# 5_5Vto5VBuck.net
KiCad netlist of a schematic drawn in Altium Designer
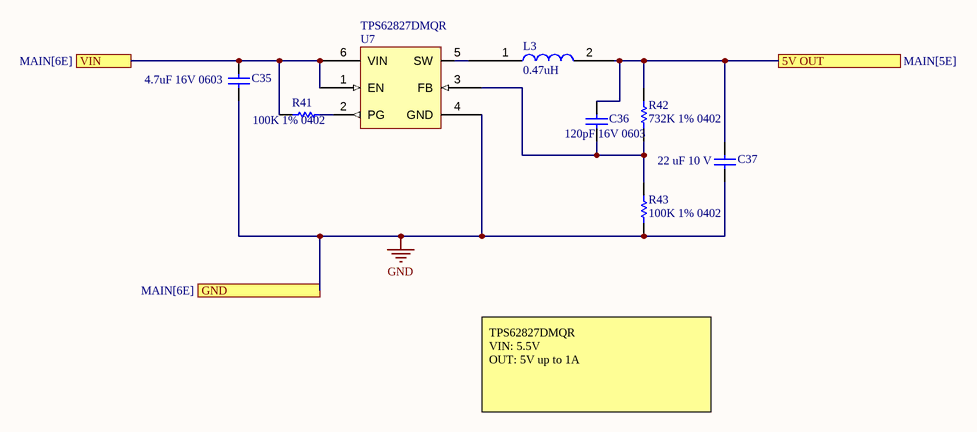
[diagram p0: 5.5Vto5VBuck.SchDoc]

(export (version "E")
  (design (tool "Eeschema 10.0.6"))
  (components
    (comp (ref "C35")
      (value "4.7uF 16V 0603")
      (footprint "CAPC0603(1608)100_N")
      (description "CAP 4.7uF 16V ±10% 0603 (1608 Metric) Thickness 1mm SMD")
      (fields (field (name "TOLERANCE") "Â±10%"))
      (libsource (lib "Altium Content Vault") (part "CAP"))
    )
    (comp (ref "C36")
      (value "120pF 16V 0603")
      (footprint "CAPC0603(1608)100_M")
      (description "CAP 120pF 16V ±5% 0603 (1608 Metric) Thickness 1mm SMD")
      (fields (field (name "TOLERANCE") "Â±5%"))
      (libsource (lib "Altium Content Vault") (part "CAP"))
    )
    (comp (ref "C37")
      (value "22 uF 10 V")
      (footprint "CAPC1608X100X20ML10")
      (description "Chip Capacitor, 22 uF, +/- 20%, 10 V, -55 to 85 degC, 0603 (1608 Metric), RoHS, Tape and Reel")
      (fields (field (name "MANUFACTURER") "TDK") (field (name "TOLERANCE") "±20%"))
      (libsource (lib "Altium Content Vault") (part "CAP-NP-2"))
    )
    (comp (ref "L3")
      (value "0.47uH")
      (footprint "RESC0603X55N")
      (description "Inductor Power Shielded Thin Film 0.47uH 20% 1MHz Metal 2.6A 0.062Ohm DCR 0603 T/R")
      (fields
        (field (name "MANUFACTURER") "TDK")
        (field (name "MANUFACTURER PART NUMBER") "TFM160808ALC-R47MTAA")
      )
      (libsource (lib "ESE516A2") (part "TFM160808ALC-R47MTAA"))
    )
    (comp (ref "R41")
      (value "100K 1% 0402")
      (footprint "RESC0402(1005)_M")
      (description "100K 0.063W 1% 0402 (1005 Metric)  SMD")
      (fields (field (name "POWER") "0.063 W") (field (name "TOLERANCE") "1 %"))
      (libsource (lib "Altium Content Vault") (part "RES"))
    )
    (comp (ref "R42")
      (value "732K 1% 0402")
      (footprint "RESC0402(1005)_M")
      (description "732K 0.063W 1% 0402 (1005 Metric)  SMD")
      (fields (field (name "TOLERANCE") "1 %") (field (name "POWER") "0.063 W"))
      (libsource (lib "Altium Content Vault") (part "RES"))
    )
    (comp (ref "R43")
      (value "100K 1% 0402")
      (footprint "RESC0402(1005)_M")
      (description "100K 0.063W 1% 0402 (1005 Metric)  SMD")
      (fields (field (name "POWER") "0.063 W") (field (name "TOLERANCE") "1 %"))
      (libsource (lib "Altium Content Vault") (part "RES"))
    )
    (comp (ref "U7")
      (value "TPS62827DMQR")
      (footprint "Texas_Instruments_DMQ0006A_MFG")
      (description "2.4V-5.5V input, 4A step-down converter with 1% Accuracy in 1.5mm x 1.5mm QFN 6-VSON-HR -40 to 125")
      (fields (field (name "MANUFACTURER") "Texas Instruments"))
      (libsource (lib "ESE516A2") (part "TPS62827DMQR"))
    )
  )
  (nets
    (net (code "1") (name "/5V OUT") (class "Default")
      (node (ref "C36") (pin "2") (pinfunction "2_2") (pintype "passive"))
      (node (ref "C37") (pin "2") (pinfunction "2_2") (pintype "passive"))
      (node (ref "L3") (pin "2") (pintype "passive"))
      (node (ref "R42") (pin "2") (pinfunction "2_2") (pintype "passive"))
    )
    (net (code "2") (name "/VIN") (class "Default")
      (node (ref "C35") (pin "2") (pinfunction "2_2") (pintype "passive"))
      (node (ref "R41") (pin "1") (pinfunction "1_1") (pintype "passive"))
      (node (ref "U7") (pin "1") (pinfunction "EN_1") (pintype "input"))
      (node (ref "U7") (pin "6") (pinfunction "VIN_6") (pintype "power_in"))
    )
    (net (code "3") (name "GND") (class "Default")
      (node (ref "C35") (pin "1") (pinfunction "1_1") (pintype "passive"))
      (node (ref "C37") (pin "1") (pinfunction "1_1") (pintype "passive"))
      (node (ref "R43") (pin "1") (pinfunction "1_1") (pintype "passive"))
      (node (ref "U7") (pin "4") (pinfunction "GND_4") (pintype "power_in"))
    )
    (net (code "4") (name "Net-(U7-FB)") (class "Default")
      (node (ref "C36") (pin "1") (pinfunction "1_1") (pintype "passive"))
      (node (ref "R42") (pin "1") (pinfunction "1_1") (pintype "passive"))
      (node (ref "R43") (pin "2") (pinfunction "2_2") (pintype "passive"))
      (node (ref "U7") (pin "3") (pinfunction "FB_3") (pintype "input"))
    )
    (net (code "5") (name "Net-(U7-PG)") (class "Default")
      (node (ref "R41") (pin "2") (pinfunction "2_2") (pintype "passive"))
      (node (ref "U7") (pin "2") (pinfunction "PG_2") (pintype "output"))
    )
    (net (code "6") (name "Net-(U7-SW)") (class "Default")
      (node (ref "L3") (pin "1") (pintype "passive"))
      (node (ref "U7") (pin "5") (pinfunction "SW_5") (pintype "power_in"))
    )
  )
)
